# NOROTAE-leddriver.net
KiCad netlist of a schematic drawn in EAGLE
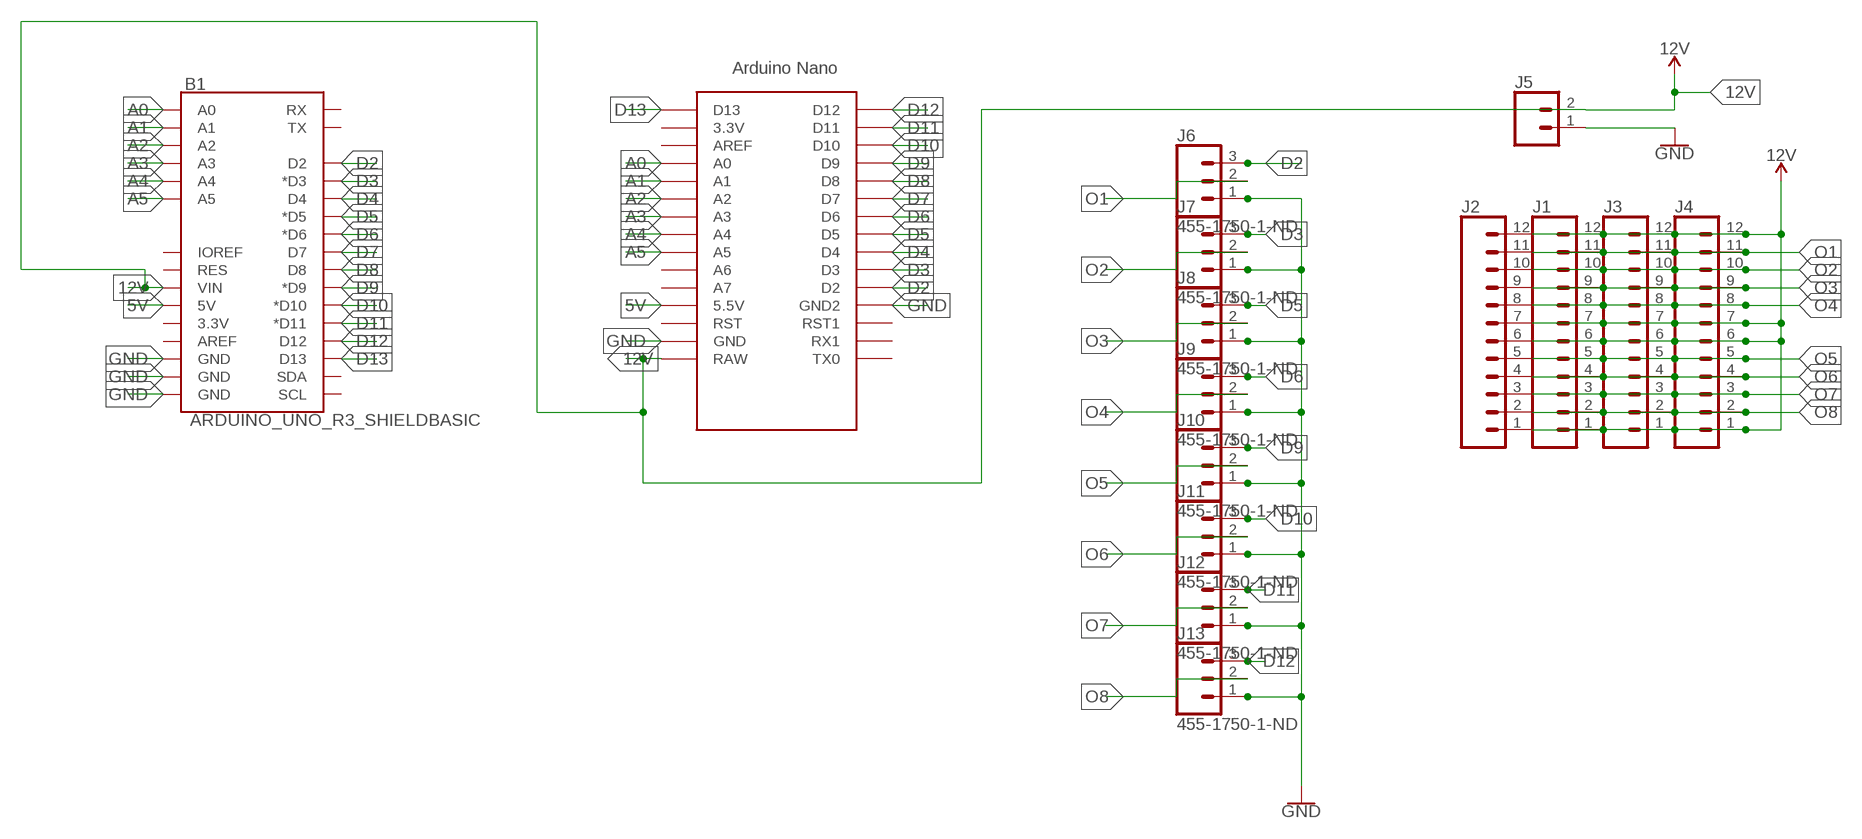
[diagram p0: schematic, sheet 1]

(export (version "E")
  (design (tool "Eeschema 10.0.6"))
  (components
    (comp (ref "B1")
      (value "ARDUINO_UNO_R3_SHIELDBASIC")
      (footprint "eagle-import:UNO_R3_SHIELD")
      (libsource (lib "eagle-import") (part "ARDUINO_UNO_R3_SHIELDBASIC"))
    )
    (comp (ref "J1")
      (value "CONN_12")
      (footprint "eagle-import:1X12")
      (libsource (lib "eagle-import") (part "CONN_12"))
    )
    (comp (ref "J2")
      (value "CONN_12")
      (footprint "eagle-import:1X12")
      (libsource (lib "eagle-import") (part "CONN_12"))
    )
    (comp (ref "J3")
      (value "CONN_12")
      (footprint "eagle-import:1X12")
      (libsource (lib "eagle-import") (part "CONN_12"))
    )
    (comp (ref "J4")
      (value "CONN_12")
      (footprint "eagle-import:1X12")
      (libsource (lib "eagle-import") (part "CONN_12"))
    )
    (comp (ref "J5")
      (value "CONN_02")
      (footprint "eagle-import:1X02")
      (libsource (lib "eagle-import") (part "CONN_02"))
    )
    (comp (ref "J6")
      (value "455-1750-1-ND")
      (footprint "eagle-import:1X03")
      (libsource (lib "eagle-import") (part "CONN_03"))
    )
    (comp (ref "J7")
      (value "455-1750-1-ND")
      (footprint "eagle-import:1X03")
      (libsource (lib "eagle-import") (part "CONN_03"))
    )
    (comp (ref "J8")
      (value "455-1750-1-ND")
      (footprint "eagle-import:1X03")
      (libsource (lib "eagle-import") (part "CONN_03"))
    )
    (comp (ref "J9")
      (value "455-1750-1-ND")
      (footprint "eagle-import:1X03")
      (libsource (lib "eagle-import") (part "CONN_03"))
    )
    (comp (ref "J10")
      (value "455-1750-1-ND")
      (footprint "eagle-import:1X03")
      (libsource (lib "eagle-import") (part "CONN_03"))
    )
    (comp (ref "J11")
      (value "455-1750-1-ND")
      (footprint "eagle-import:1X03")
      (libsource (lib "eagle-import") (part "CONN_03"))
    )
    (comp (ref "J12")
      (value "455-1750-1-ND")
      (footprint "eagle-import:1X03")
      (libsource (lib "eagle-import") (part "CONN_03"))
    )
    (comp (ref "J13")
      (value "455-1750-1-ND")
      (footprint "eagle-import:1X03")
      (libsource (lib "eagle-import") (part "CONN_03"))
    )
    (comp (ref "U$1")
      (value "NANO")
      (footprint "eagle-import:NANO")
      (libsource (lib "eagle-import") (part "NANO"))
    )
  )
  (nets
    (net (code "1") (name "5V") (class "Default")
      (node (ref "B1") (pin "5V") (pinfunction "5V_5V") (pintype "bidirectional"))
      (node (ref "U$1") (pin "5V") (pinfunction "5.5V_5V") (pintype "bidirectional"))
    )
    (net (code "2") (name "12V") (class "Default")
      (node (ref "B1") (pin "VIN") (pinfunction "VIN_VIN") (pintype "bidirectional"))
      (node (ref "J1") (pin "1") (pinfunction "1_1") (pintype "passive"))
      (node (ref "J1") (pin "12") (pinfunction "12_12") (pintype "passive"))
      (node (ref "J1") (pin "6") (pinfunction "6_6") (pintype "passive"))
      (node (ref "J1") (pin "7") (pinfunction "7_7") (pintype "passive"))
      (node (ref "J2") (pin "1") (pinfunction "1_1") (pintype "passive"))
      (node (ref "J2") (pin "12") (pinfunction "12_12") (pintype "passive"))
      (node (ref "J2") (pin "6") (pinfunction "6_6") (pintype "passive"))
      (node (ref "J2") (pin "7") (pinfunction "7_7") (pintype "passive"))
      (node (ref "J3") (pin "1") (pinfunction "1_1") (pintype "passive"))
      (node (ref "J3") (pin "12") (pinfunction "12_12") (pintype "passive"))
      (node (ref "J3") (pin "6") (pinfunction "6_6") (pintype "passive"))
      (node (ref "J3") (pin "7") (pinfunction "7_7") (pintype "passive"))
      (node (ref "J4") (pin "1") (pinfunction "1_1") (pintype "passive"))
      (node (ref "J4") (pin "12") (pinfunction "12_12") (pintype "passive"))
      (node (ref "J4") (pin "6") (pinfunction "6_6") (pintype "passive"))
      (node (ref "J4") (pin "7") (pinfunction "7_7") (pintype "passive"))
      (node (ref "J5") (pin "2") (pinfunction "2_2") (pintype "passive"))
      (node (ref "U$1") (pin "RAW") (pinfunction "RAW_RAW") (pintype "bidirectional"))
    )
    (net (code "3") (name "A0") (class "Default")
      (node (ref "B1") (pin "A0") (pinfunction "A0_A0") (pintype "bidirectional"))
      (node (ref "U$1") (pin "A0") (pinfunction "A0_A0") (pintype "bidirectional"))
    )
    (net (code "4") (name "A1") (class "Default")
      (node (ref "B1") (pin "A1") (pinfunction "A1_A1") (pintype "bidirectional"))
      (node (ref "U$1") (pin "A1") (pinfunction "A1_A1") (pintype "bidirectional"))
    )
    (net (code "5") (name "A2") (class "Default")
      (node (ref "B1") (pin "A2") (pinfunction "A2_A2") (pintype "bidirectional"))
      (node (ref "U$1") (pin "A2") (pinfunction "A2_A2") (pintype "bidirectional"))
    )
    (net (code "6") (name "A3") (class "Default")
      (node (ref "B1") (pin "A3") (pinfunction "A3_A3") (pintype "bidirectional"))
      (node (ref "U$1") (pin "A3") (pinfunction "A3_A3") (pintype "bidirectional"))
    )
    (net (code "7") (name "A4") (class "Default")
      (node (ref "B1") (pin "A4") (pinfunction "A4_A4") (pintype "bidirectional"))
      (node (ref "U$1") (pin "A4") (pinfunction "A4_A4") (pintype "bidirectional"))
    )
    (net (code "8") (name "A5") (class "Default")
      (node (ref "B1") (pin "A5") (pinfunction "A5_A5") (pintype "bidirectional"))
      (node (ref "U$1") (pin "A5") (pinfunction "A5_A5") (pintype "bidirectional"))
    )
    (net (code "9") (name "D2") (class "Default")
      (node (ref "B1") (pin "D2") (pinfunction "D2_D2") (pintype "bidirectional"))
      (node (ref "J6") (pin "3") (pinfunction "3_3") (pintype "passive"))
      (node (ref "U$1") (pin "D2") (pinfunction "D2_D2") (pintype "bidirectional"))
    )
    (net (code "10") (name "D3") (class "Default")
      (node (ref "B1") (pin "D3") (pinfunction "*D3_D3") (pintype "bidirectional"))
      (node (ref "J7") (pin "3") (pinfunction "3_3") (pintype "passive"))
      (node (ref "U$1") (pin "D3") (pinfunction "D3_D3") (pintype "bidirectional"))
    )
    (net (code "11") (name "D4") (class "Default")
      (node (ref "B1") (pin "D4") (pinfunction "D4_D4") (pintype "bidirectional"))
      (node (ref "U$1") (pin "D4") (pinfunction "D4_D4") (pintype "bidirectional"))
    )
    (net (code "12") (name "D5") (class "Default")
      (node (ref "B1") (pin "D5") (pinfunction "*D5_D5") (pintype "bidirectional"))
      (node (ref "J8") (pin "3") (pinfunction "3_3") (pintype "passive"))
      (node (ref "U$1") (pin "D5") (pinfunction "D5_D5") (pintype "bidirectional"))
    )
    (net (code "13") (name "D6") (class "Default")
      (node (ref "B1") (pin "D6") (pinfunction "*D6_D6") (pintype "bidirectional"))
      (node (ref "J9") (pin "3") (pinfunction "3_3") (pintype "passive"))
      (node (ref "U$1") (pin "D6") (pinfunction "D6_D6") (pintype "bidirectional"))
    )
    (net (code "14") (name "D7") (class "Default")
      (node (ref "B1") (pin "D7") (pinfunction "D7_D7") (pintype "bidirectional"))
      (node (ref "U$1") (pin "D7") (pinfunction "D7_D7") (pintype "bidirectional"))
    )
    (net (code "15") (name "D8") (class "Default")
      (node (ref "B1") (pin "D8") (pinfunction "D8_D8") (pintype "bidirectional"))
      (node (ref "U$1") (pin "D8") (pinfunction "D8_D8") (pintype "bidirectional"))
    )
    (net (code "16") (name "D9") (class "Default")
      (node (ref "B1") (pin "D9") (pinfunction "*D9_D9") (pintype "bidirectional"))
      (node (ref "J10") (pin "3") (pinfunction "3_3") (pintype "passive"))
      (node (ref "U$1") (pin "D9") (pinfunction "D9_D9") (pintype "bidirectional"))
    )
    (net (code "17") (name "D10") (class "Default")
      (node (ref "B1") (pin "D10") (pinfunction "*D10_D10") (pintype "bidirectional"))
      (node (ref "J11") (pin "3") (pinfunction "3_3") (pintype "passive"))
      (node (ref "U$1") (pin "D10") (pinfunction "D10_D10") (pintype "bidirectional"))
    )
    (net (code "18") (name "D11") (class "Default")
      (node (ref "B1") (pin "D11") (pinfunction "*D11_D11") (pintype "bidirectional"))
      (node (ref "J12") (pin "3") (pinfunction "3_3") (pintype "passive"))
      (node (ref "U$1") (pin "D11") (pinfunction "D11_D11") (pintype "bidirectional"))
    )
    (net (code "19") (name "D12") (class "Default")
      (node (ref "B1") (pin "D12") (pinfunction "D12_D12") (pintype "bidirectional"))
      (node (ref "J13") (pin "3") (pinfunction "3_3") (pintype "passive"))
      (node (ref "U$1") (pin "D12") (pinfunction "D12_D12") (pintype "bidirectional"))
    )
    (net (code "20") (name "D13") (class "Default")
      (node (ref "B1") (pin "D13") (pinfunction "D13_D13") (pintype "bidirectional"))
      (node (ref "U$1") (pin "D13") (pinfunction "D13_D13") (pintype "bidirectional"))
    )
    (net (code "21") (name "GND") (class "Default")
      (node (ref "B1") (pin "GND@0") (pinfunction "GND_GND@0") (pintype "bidirectional"))
      (node (ref "B1") (pin "GND@1") (pinfunction "GND_GND@1") (pintype "bidirectional"))
      (node (ref "B1") (pin "GND@2") (pinfunction "GND_GND@2") (pintype "bidirectional"))
      (node (ref "J10") (pin "1") (pinfunction "1_1") (pintype "passive"))
      (node (ref "J11") (pin "1") (pinfunction "1_1") (pintype "passive"))
      (node (ref "J12") (pin "1") (pinfunction "1_1") (pintype "passive"))
      (node (ref "J13") (pin "1") (pinfunction "1_1") (pintype "passive"))
      (node (ref "J5") (pin "1") (pinfunction "1_1") (pintype "passive"))
      (node (ref "J6") (pin "1") (pinfunction "1_1") (pintype "passive"))
      (node (ref "J7") (pin "1") (pinfunction "1_1") (pintype "passive"))
      (node (ref "J8") (pin "1") (pinfunction "1_1") (pintype "passive"))
      (node (ref "J9") (pin "1") (pinfunction "1_1") (pintype "passive"))
      (node (ref "U$1") (pin "GND") (pinfunction "GND_GND") (pintype "bidirectional"))
      (node (ref "U$1") (pin "GND1") (pinfunction "GND2_GND1") (pintype "bidirectional"))
    )
    (net (code "22") (name "O1") (class "Default")
      (node (ref "J1") (pin "11") (pinfunction "11_11") (pintype "passive"))
      (node (ref "J2") (pin "11") (pinfunction "11_11") (pintype "passive"))
      (node (ref "J3") (pin "11") (pinfunction "11_11") (pintype "passive"))
      (node (ref "J4") (pin "11") (pinfunction "11_11") (pintype "passive"))
      (node (ref "J6") (pin "2") (pinfunction "2_2") (pintype "passive"))
    )
    (net (code "23") (name "O2") (class "Default")
      (node (ref "J1") (pin "10") (pinfunction "10_10") (pintype "passive"))
      (node (ref "J2") (pin "10") (pinfunction "10_10") (pintype "passive"))
      (node (ref "J3") (pin "10") (pinfunction "10_10") (pintype "passive"))
      (node (ref "J4") (pin "10") (pinfunction "10_10") (pintype "passive"))
      (node (ref "J7") (pin "2") (pinfunction "2_2") (pintype "passive"))
    )
    (net (code "24") (name "O3") (class "Default")
      (node (ref "J1") (pin "9") (pinfunction "9_9") (pintype "passive"))
      (node (ref "J2") (pin "9") (pinfunction "9_9") (pintype "passive"))
      (node (ref "J3") (pin "9") (pinfunction "9_9") (pintype "passive"))
      (node (ref "J4") (pin "9") (pinfunction "9_9") (pintype "passive"))
      (node (ref "J8") (pin "2") (pinfunction "2_2") (pintype "passive"))
    )
    (net (code "25") (name "O4") (class "Default")
      (node (ref "J1") (pin "8") (pinfunction "8_8") (pintype "passive"))
      (node (ref "J2") (pin "8") (pinfunction "8_8") (pintype "passive"))
      (node (ref "J3") (pin "8") (pinfunction "8_8") (pintype "passive"))
      (node (ref "J4") (pin "8") (pinfunction "8_8") (pintype "passive"))
      (node (ref "J9") (pin "2") (pinfunction "2_2") (pintype "passive"))
    )
    (net (code "26") (name "O5") (class "Default")
      (node (ref "J1") (pin "5") (pinfunction "5_5") (pintype "passive"))
      (node (ref "J10") (pin "2") (pinfunction "2_2") (pintype "passive"))
      (node (ref "J2") (pin "5") (pinfunction "5_5") (pintype "passive"))
      (node (ref "J3") (pin "5") (pinfunction "5_5") (pintype "passive"))
      (node (ref "J4") (pin "5") (pinfunction "5_5") (pintype "passive"))
    )
    (net (code "27") (name "O6") (class "Default")
      (node (ref "J1") (pin "4") (pinfunction "4_4") (pintype "passive"))
      (node (ref "J11") (pin "2") (pinfunction "2_2") (pintype "passive"))
      (node (ref "J2") (pin "4") (pinfunction "4_4") (pintype "passive"))
      (node (ref "J3") (pin "4") (pinfunction "4_4") (pintype "passive"))
      (node (ref "J4") (pin "4") (pinfunction "4_4") (pintype "passive"))
    )
    (net (code "28") (name "O7") (class "Default")
      (node (ref "J1") (pin "3") (pinfunction "3_3") (pintype "passive"))
      (node (ref "J12") (pin "2") (pinfunction "2_2") (pintype "passive"))
      (node (ref "J2") (pin "3") (pinfunction "3_3") (pintype "passive"))
      (node (ref "J3") (pin "3") (pinfunction "3_3") (pintype "passive"))
      (node (ref "J4") (pin "3") (pinfunction "3_3") (pintype "passive"))
    )
    (net (code "29") (name "O8") (class "Default")
      (node (ref "J1") (pin "2") (pinfunction "2_2") (pintype "passive"))
      (node (ref "J13") (pin "2") (pinfunction "2_2") (pintype "passive"))
      (node (ref "J2") (pin "2") (pinfunction "2_2") (pintype "passive"))
      (node (ref "J3") (pin "2") (pinfunction "2_2") (pintype "passive"))
      (node (ref "J4") (pin "2") (pinfunction "2_2") (pintype "passive"))
    )
    (net (code "30") (name "unconnected-(B1-Pad3.3V)") (class "Default")
      (node (ref "B1") (pin "3.3V") (pinfunction "3.3V_3.3V") (pintype "bidirectional"))
    )
    (net (code "31") (name "unconnected-(B1-PadAREF)") (class "Default")
      (node (ref "B1") (pin "AREF") (pinfunction "AREF_AREF") (pintype "bidirectional"))
    )
    (net (code "32") (name "unconnected-(B1-PadIOREF)") (class "Default")
      (node (ref "B1") (pin "IOREF") (pinfunction "IOREF_IOREF") (pintype "bidirectional"))
    )
    (net (code "33") (name "unconnected-(B1-PadRES)") (class "Default")
      (node (ref "B1") (pin "RES") (pinfunction "RES_RES") (pintype "bidirectional"))
    )
    (net (code "34") (name "unconnected-(B1-PadRX)") (class "Default")
      (node (ref "B1") (pin "RX") (pinfunction "RX_RX") (pintype "bidirectional"))
    )
    (net (code "35") (name "unconnected-(B1-PadSCL)") (class "Default")
      (node (ref "B1") (pin "SCL") (pinfunction "SCL_SCL") (pintype "bidirectional"))
    )
    (net (code "36") (name "unconnected-(B1-PadSDA)") (class "Default")
      (node (ref "B1") (pin "SDA") (pinfunction "SDA_SDA") (pintype "bidirectional"))
    )
    (net (code "37") (name "unconnected-(B1-PadTX)") (class "Default")
      (node (ref "B1") (pin "TX") (pinfunction "TX_TX") (pintype "bidirectional"))
    )
    (net (code "38") (name "unconnected-(U$1-Pad3.3V)") (class "Default")
      (node (ref "U$1") (pin "3.3V") (pinfunction "3.3V_3.3V") (pintype "bidirectional"))
    )
    (net (code "39") (name "unconnected-(U$1-PadA6)") (class "Default")
      (node (ref "U$1") (pin "A6") (pinfunction "A6_A6") (pintype "bidirectional"))
    )
    (net (code "40") (name "unconnected-(U$1-PadA7)") (class "Default")
      (node (ref "U$1") (pin "A7") (pinfunction "A7_A7") (pintype "bidirectional"))
    )
    (net (code "41") (name "unconnected-(U$1-PadAREF)") (class "Default")
      (node (ref "U$1") (pin "AREF") (pinfunction "AREF_AREF") (pintype "bidirectional"))
    )
    (net (code "42") (name "unconnected-(U$1-PadICSP1)") (class "Default")
      (node (ref "U$1") (pin "ICSP1") (pinfunction "ICSP1_ICSP1") (pintype "bidirectional"))
    )
    (net (code "43") (name "unconnected-(U$1-PadICSP2)") (class "Default")
      (node (ref "U$1") (pin "ICSP2") (pinfunction "ICSP2_ICSP2") (pintype "bidirectional"))
    )
    (net (code "44") (name "unconnected-(U$1-PadICSP3)") (class "Default")
      (node (ref "U$1") (pin "ICSP3") (pinfunction "ICSP3_ICSP3") (pintype "bidirectional"))
    )
    (net (code "45") (name "unconnected-(U$1-PadICSP4)") (class "Default")
      (node (ref "U$1") (pin "ICSP4") (pinfunction "ICSP4_ICSP4") (pintype "bidirectional"))
    )
    (net (code "46") (name "unconnected-(U$1-PadICSP5)") (class "Default")
      (node (ref "U$1") (pin "ICSP5") (pinfunction "ICSP5_ICSP5") (pintype "bidirectional"))
    )
    (net (code "47") (name "unconnected-(U$1-PadICSP6)") (class "Default")
      (node (ref "U$1") (pin "ICSP6") (pinfunction "ICSP6_ICSP6") (pintype "bidirectional"))
    )
    (net (code "48") (name "unconnected-(U$1-PadRST)") (class "Default")
      (node (ref "U$1") (pin "RST") (pinfunction "RST_RST") (pintype "bidirectional"))
    )
    (net (code "49") (name "unconnected-(U$1-PadRST1)") (class "Default")
      (node (ref "U$1") (pin "RST1") (pinfunction "RST1_RST1") (pintype "bidirectional"))
    )
    (net (code "50") (name "unconnected-(U$1-PadRX1)") (class "Default")
      (node (ref "U$1") (pin "RX1") (pinfunction "RX1_RX1") (pintype "bidirectional"))
    )
    (net (code "51") (name "unconnected-(U$1-PadTX0)") (class "Default")
      (node (ref "U$1") (pin "TX0") (pinfunction "TX0_TX0") (pintype "bidirectional"))
    )
  )
)
